# 4-Connector.net
KiCad netlist of a schematic drawn in Altium Designer
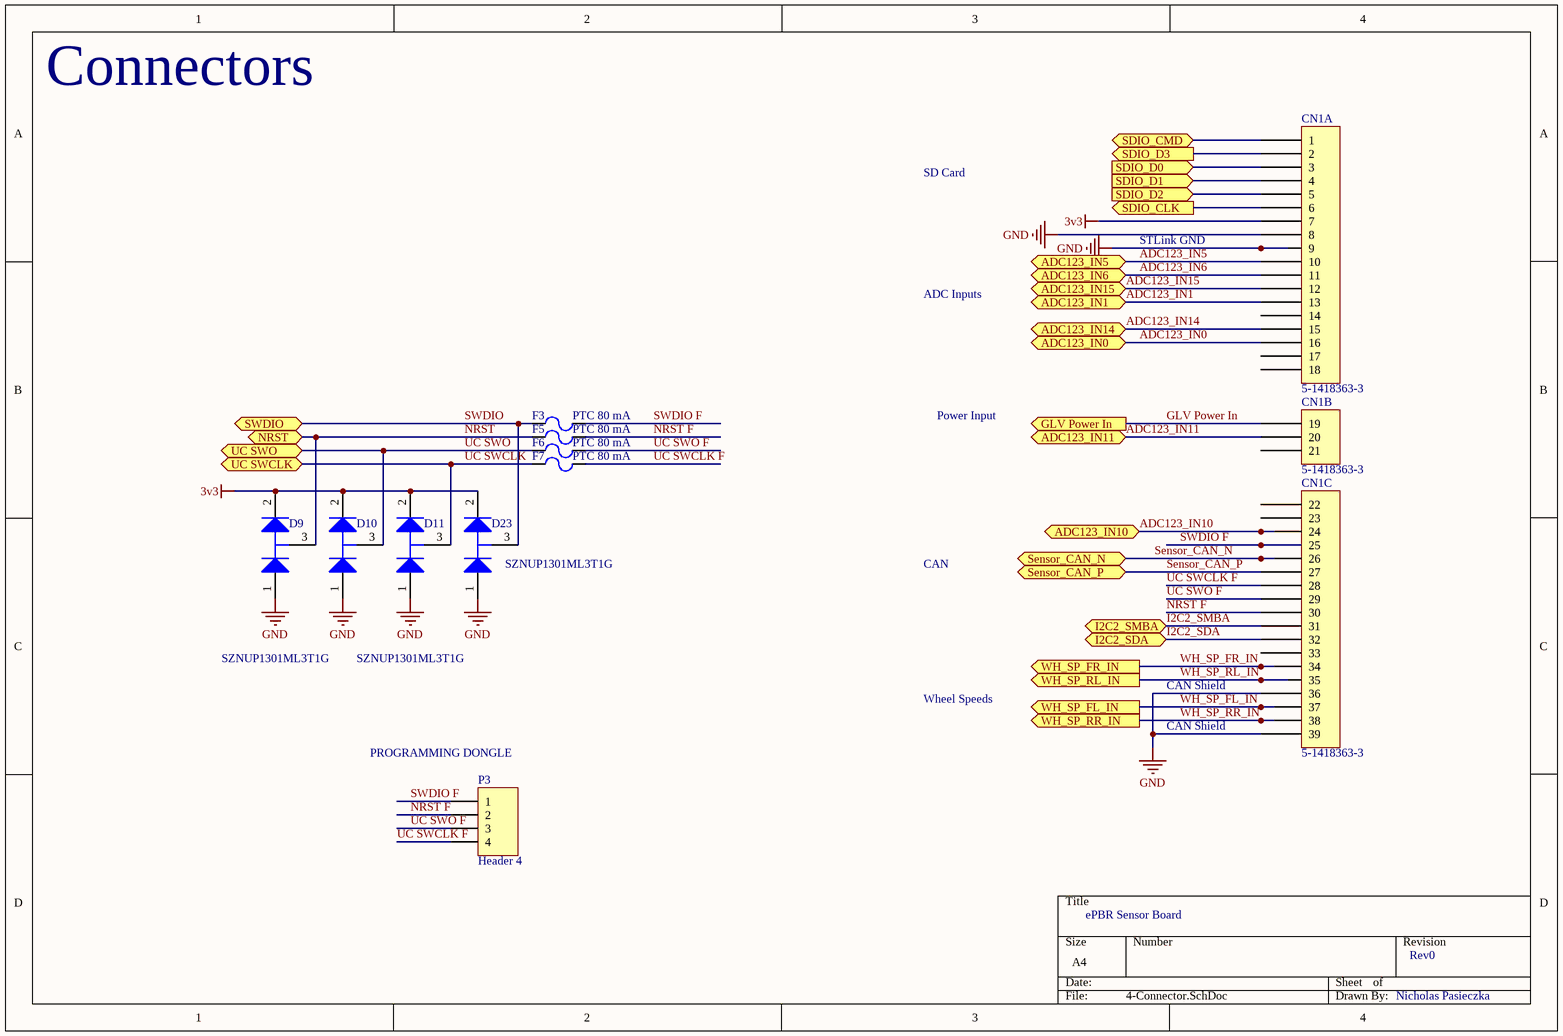
[diagram p0: 4-Connector.SchDoc]

(export (version "E")
  (design (tool "Eeschema 10.0.6"))
  (components
    (comp (ref "CN1")
      (value "5-1418363-3")
      (footprint "5-1418363-3")
      (description "Levyseal 90 degree 39 pin header")
      (libsource (lib "VCB20") (part "5-1418363-3"))
    )
    (comp (ref "D9")
      (value "SZNUP1301ML3T1G")
      (footprint "ONSC-SOT-23-3-318-08_V")
      (fields (field (name "MANUFACTURER") "On Semiconductor"))
      (libsource (lib "Altium Content Vault") (part "ONSC-NUP1301-SOT-23-3-318-08"))
    )
    (comp (ref "D10")
      (value "SZNUP1301ML3T1G")
      (footprint "ONSC-SOT-23-3-318-08_V")
      (fields (field (name "MANUFACTURER") "On Semiconductor"))
      (libsource (lib "Altium Content Vault") (part "ONSC-NUP1301-SOT-23-3-318-08"))
    )
    (comp (ref "D11")
      (value "SZNUP1301ML3T1G")
      (footprint "ONSC-SOT-23-3-318-08_V")
      (fields (field (name "MANUFACTURER") "On Semiconductor"))
      (libsource (lib "Altium Content Vault") (part "ONSC-NUP1301-SOT-23-3-318-08"))
    )
    (comp (ref "D23")
      (value "SZNUP1301ML3T1G")
      (footprint "ONSC-SOT-23-3-318-08_V")
      (fields (field (name "MANUFACTURER") "On Semiconductor"))
      (libsource (lib "Altium Content Vault") (part "ONSC-NUP1301-SOT-23-3-318-08"))
    )
    (comp (ref "F3")
      (value "PTC 80 mA")
      (footprint "0603 fuse")
      (description "0ZCM0008FF2G")
      (libsource (lib "VCU Library") (part "PTC fuse 80mA 0ZCM0008FF2G"))
    )
    (comp (ref "F5")
      (value "PTC 80 mA")
      (footprint "0603 fuse")
      (description "0ZCM0008FF2G")
      (libsource (lib "VCU Library") (part "PTC fuse 80mA 0ZCM0008FF2G"))
    )
    (comp (ref "F6")
      (value "PTC 80 mA")
      (footprint "0603 fuse")
      (description "0ZCM0008FF2G")
      (libsource (lib "VCU Library") (part "PTC fuse 80mA 0ZCM0008FF2G"))
    )
    (comp (ref "F7")
      (value "PTC 80 mA")
      (footprint "0603 fuse")
      (description "0ZCM0008FF2G")
      (libsource (lib "VCU Library") (part "PTC fuse 80mA 0ZCM0008FF2G"))
    )
    (comp (ref "P3")
      (value "Header 4")
      (footprint "HDR1X4")
      (description "Header, 4-Pin")
      (fields (field (name "PUBLISHER") "Altium Limited"))
      (libsource (lib "Miscellaneous Connectors") (part "Header 4"))
    )
  )
  (nets
    (net (code "1") (name "/ADC123_IN0") (class "Default")
      (node (ref "CN1") (pin "16") (pinfunction "16_16") (pintype "passive"))
    )
    (net (code "2") (name "/ADC123_IN1") (class "Default")
      (node (ref "CN1") (pin "13") (pinfunction "13_13") (pintype "passive"))
    )
    (net (code "3") (name "/ADC123_IN5") (class "Default")
      (node (ref "CN1") (pin "10") (pinfunction "10_10") (pintype "passive"))
    )
    (net (code "4") (name "/ADC123_IN6") (class "Default")
      (node (ref "CN1") (pin "11") (pinfunction "11_11") (pintype "passive"))
    )
    (net (code "5") (name "/ADC123_IN10") (class "Default")
      (node (ref "CN1") (pin "24") (pinfunction "24_24") (pintype "passive"))
    )
    (net (code "6") (name "/ADC123_IN11") (class "Default")
      (node (ref "CN1") (pin "20") (pinfunction "20_20") (pintype "passive"))
    )
    (net (code "7") (name "/ADC123_IN14") (class "Default")
      (node (ref "CN1") (pin "15") (pinfunction "15_15") (pintype "passive"))
    )
    (net (code "8") (name "/ADC123_IN15") (class "Default")
      (node (ref "CN1") (pin "12") (pinfunction "12_12") (pintype "passive"))
    )
    (net (code "9") (name "/GLV Power In") (class "Default")
      (node (ref "CN1") (pin "19") (pinfunction "19_19") (pintype "passive"))
    )
    (net (code "10") (name "/I2C2_SDA") (class "Default")
      (node (ref "CN1") (pin "32") (pinfunction "32_32") (pintype "passive"))
    )
    (net (code "11") (name "/I2C2_SMBA") (class "Default")
      (node (ref "CN1") (pin "31") (pinfunction "31_31") (pintype "passive"))
    )
    (net (code "12") (name "/NRST") (class "Default")
      (node (ref "D9") (pin "3") (pinfunction "K/A_3") (pintype "passive"))
      (node (ref "F5") (pin "1") (pinfunction "1_1") (pintype "passive"))
    )
    (net (code "13") (name "/NRST F") (class "Default")
      (node (ref "CN1") (pin "30") (pinfunction "30_30") (pintype "passive"))
      (node (ref "F5") (pin "2") (pinfunction "2_2") (pintype "passive"))
      (node (ref "P3") (pin "2") (pinfunction "2_2") (pintype "passive"))
    )
    (net (code "14") (name "/SDIO_CLK") (class "Default")
      (node (ref "CN1") (pin "6") (pinfunction "6_6") (pintype "passive"))
    )
    (net (code "15") (name "/SDIO_CMD") (class "Default")
      (node (ref "CN1") (pin "1") (pinfunction "1_1") (pintype "passive"))
    )
    (net (code "16") (name "/SDIO_D0") (class "Default")
      (node (ref "CN1") (pin "3") (pinfunction "3_3") (pintype "passive"))
    )
    (net (code "17") (name "/SDIO_D1") (class "Default")
      (node (ref "CN1") (pin "4") (pinfunction "4_4") (pintype "passive"))
    )
    (net (code "18") (name "/SDIO_D2") (class "Default")
      (node (ref "CN1") (pin "5") (pinfunction "5_5") (pintype "passive"))
    )
    (net (code "19") (name "/SDIO_D3") (class "Default")
      (node (ref "CN1") (pin "2") (pinfunction "2_2") (pintype "passive"))
    )
    (net (code "20") (name "/SWDIO") (class "Default")
      (node (ref "D23") (pin "3") (pinfunction "K/A_3") (pintype "passive"))
      (node (ref "F3") (pin "1") (pinfunction "1_1") (pintype "passive"))
    )
    (net (code "21") (name "/SWDIO F") (class "Default")
      (node (ref "CN1") (pin "25") (pinfunction "25_25") (pintype "passive"))
      (node (ref "F3") (pin "2") (pinfunction "2_2") (pintype "passive"))
      (node (ref "P3") (pin "1") (pinfunction "1_1") (pintype "passive"))
    )
    (net (code "22") (name "/Sensor_CAN_N") (class "Default")
      (node (ref "CN1") (pin "26") (pinfunction "26_26") (pintype "passive"))
    )
    (net (code "23") (name "/Sensor_CAN_P") (class "Default")
      (node (ref "CN1") (pin "27") (pinfunction "27_27") (pintype "passive"))
    )
    (net (code "24") (name "/UC SWCLK") (class "Default")
      (node (ref "D11") (pin "3") (pinfunction "K/A_3") (pintype "passive"))
      (node (ref "F7") (pin "1") (pinfunction "1_1") (pintype "passive"))
    )
    (net (code "25") (name "/UC SWCLK F") (class "Default")
      (node (ref "CN1") (pin "28") (pinfunction "28_28") (pintype "passive"))
      (node (ref "F7") (pin "2") (pinfunction "2_2") (pintype "passive"))
      (node (ref "P3") (pin "4") (pinfunction "4_4") (pintype "passive"))
    )
    (net (code "26") (name "/UC SWO") (class "Default")
      (node (ref "D10") (pin "3") (pinfunction "K/A_3") (pintype "passive"))
      (node (ref "F6") (pin "1") (pinfunction "1_1") (pintype "passive"))
    )
    (net (code "27") (name "/UC SWO F") (class "Default")
      (node (ref "CN1") (pin "29") (pinfunction "29_29") (pintype "passive"))
      (node (ref "F6") (pin "2") (pinfunction "2_2") (pintype "passive"))
      (node (ref "P3") (pin "3") (pinfunction "3_3") (pintype "passive"))
    )
    (net (code "28") (name "/WH_SP_FL_IN") (class "Default")
      (node (ref "CN1") (pin "37") (pinfunction "37_37") (pintype "passive"))
    )
    (net (code "29") (name "/WH_SP_FR_IN") (class "Default")
      (node (ref "CN1") (pin "34") (pinfunction "34_34") (pintype "passive"))
    )
    (net (code "30") (name "/WH_SP_RL_IN") (class "Default")
      (node (ref "CN1") (pin "35") (pinfunction "35_35") (pintype "passive"))
    )
    (net (code "31") (name "/WH_SP_RR_IN") (class "Default")
      (node (ref "CN1") (pin "38") (pinfunction "38_38") (pintype "passive"))
    )
    (net (code "32") (name "3v3") (class "Default")
      (node (ref "CN1") (pin "7") (pinfunction "7_7") (pintype "passive"))
      (node (ref "D10") (pin "2") (pinfunction "K_2") (pintype "passive"))
      (node (ref "D11") (pin "2") (pinfunction "K_2") (pintype "passive"))
      (node (ref "D23") (pin "2") (pinfunction "K_2") (pintype "passive"))
      (node (ref "D9") (pin "2") (pinfunction "K_2") (pintype "passive"))
    )
    (net (code "33") (name "GND") (class "Default")
      (node (ref "CN1") (pin "36") (pinfunction "36_36") (pintype "passive"))
      (node (ref "CN1") (pin "39") (pinfunction "39_39") (pintype "passive"))
      (node (ref "CN1") (pin "8") (pinfunction "8_8") (pintype "passive"))
      (node (ref "CN1") (pin "9") (pinfunction "9_9") (pintype "passive"))
      (node (ref "D10") (pin "1") (pinfunction "A_1") (pintype "passive"))
      (node (ref "D11") (pin "1") (pinfunction "A_1") (pintype "passive"))
      (node (ref "D23") (pin "1") (pinfunction "A_1") (pintype "passive"))
      (node (ref "D9") (pin "1") (pinfunction "A_1") (pintype "passive"))
    )
    (net (code "34") (name "unconnected-(CN1-Pad14)") (class "Default")
      (node (ref "CN1") (pin "14") (pinfunction "14_14") (pintype "passive"))
    )
    (net (code "35") (name "unconnected-(CN1-Pad17)") (class "Default")
      (node (ref "CN1") (pin "17") (pinfunction "17_17") (pintype "passive"))
    )
    (net (code "36") (name "unconnected-(CN1-Pad18)") (class "Default")
      (node (ref "CN1") (pin "18") (pinfunction "18_18") (pintype "passive"))
    )
    (net (code "37") (name "unconnected-(CN1-Pad21)") (class "Default")
      (node (ref "CN1") (pin "21") (pinfunction "21_21") (pintype "passive"))
    )
    (net (code "38") (name "unconnected-(CN1-Pad22)") (class "Default")
      (node (ref "CN1") (pin "22") (pinfunction "22_22") (pintype "passive"))
    )
    (net (code "39") (name "unconnected-(CN1-Pad23)") (class "Default")
      (node (ref "CN1") (pin "23") (pinfunction "23_23") (pintype "passive"))
    )
    (net (code "40") (name "unconnected-(CN1-Pad33)") (class "Default")
      (node (ref "CN1") (pin "33") (pinfunction "33_33") (pintype "passive"))
    )
  )
)
